# 03_UI_Outputs.net
KiCad netlist of a schematic drawn in Altium Designer
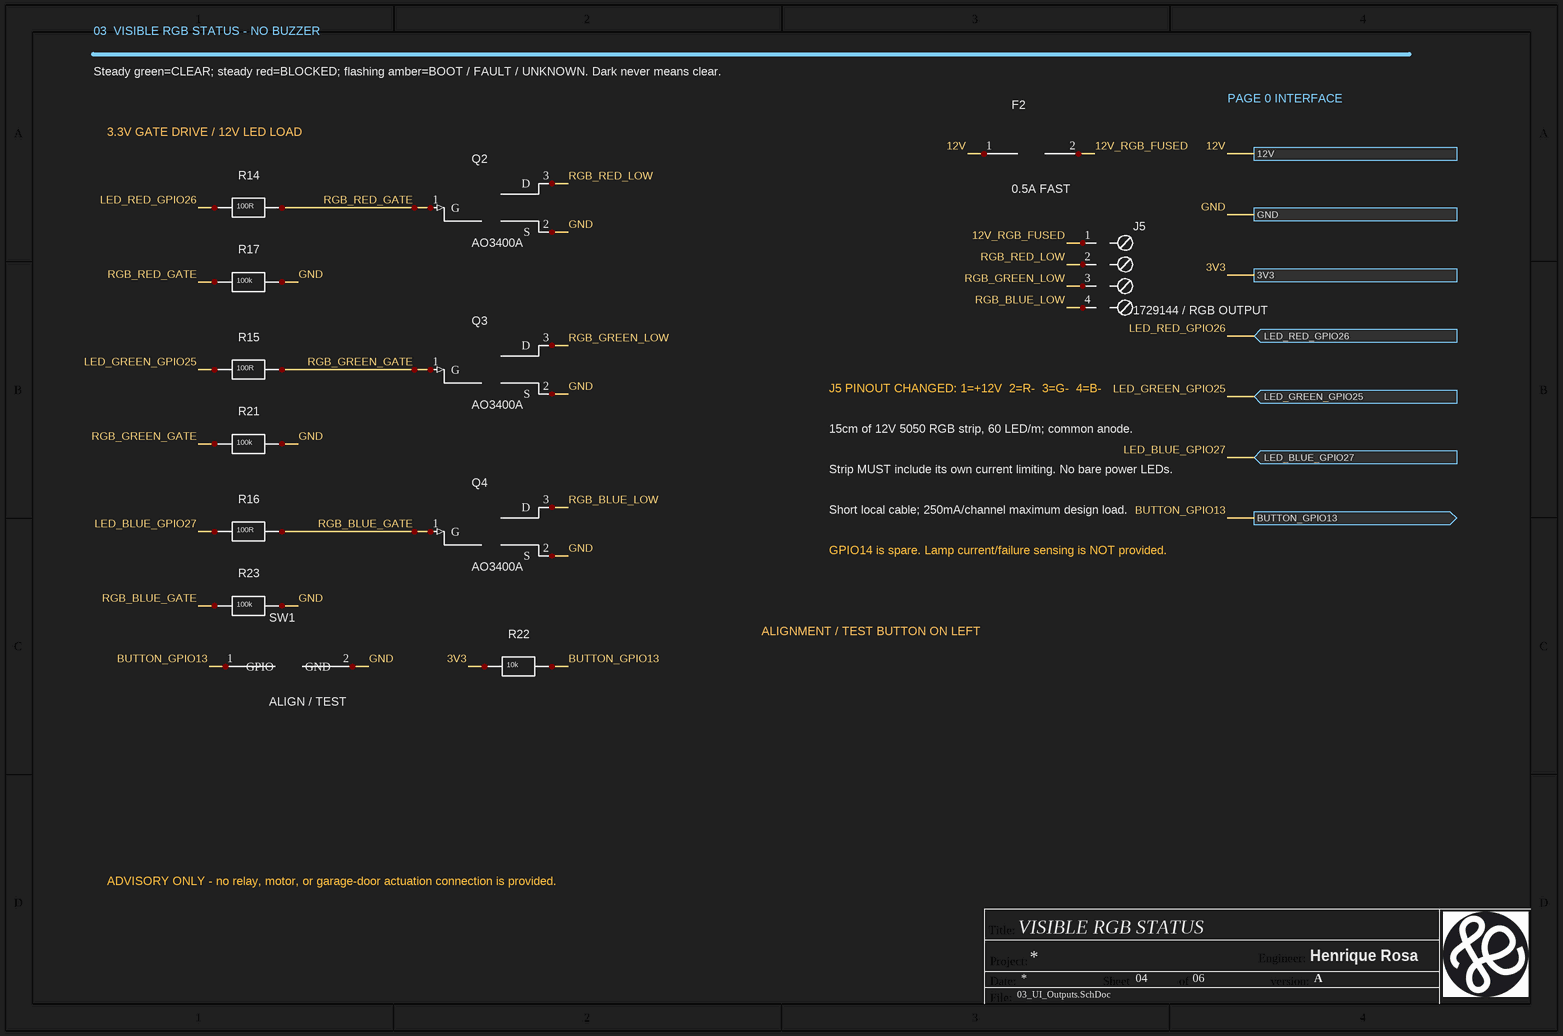
[diagram p0: 03_UI_Outputs.SchDoc]

(export (version "E")
  (design (tool "Eeschema 10.0.6"))
  (components
    (comp (ref "F2")
      (value "0.5A FAST")
      (footprint "PinRepairFootprints:LITTELFUSE_0451_2410")
      (description "RGB cable branch fuse; verify fault clearing with selected supply")
      (fields
        (field (name "MANUFACTURER") "Littelfuse")
        (field (name "MANUFACTURER PART NUMBER") "0451.500MRL")
      )
      (libsource (lib "ReviewedComponents_20260912-233454") (part "0451_500MRL__F2_view"))
    )
    (comp (ref "J5")
      (value "1729144 / RGB OUTPUT")
      (footprint "PartSpecificFootprints:PHOENIX_1729144_MKDSN_4_508")
      (description "Common-anode analogue RGB strip; NOT addressable")
      (fields
        (field (name "MANUFACTURER") "Phoenix Contact")
        (field (name "MANUFACTURER PART NUMBER") "1729144")
      )
      (libsource (lib "ReviewedComponents_20260912-233454") (part "1729144__J5_view"))
    )
    (comp (ref "Q2")
      (value "AO3400A")
      (footprint "PinRepairFootprints:AO3400A_G1_S2_D3")
      (description "30V NMOS; Rds(on) specified at Vgs=2.5V; limit load to 250mA/channel")
      (fields (field (name "MANUFACTURER") "Alpha and Omega Semiconductor"))
      (libsource (lib "ReviewedComponents_20260912-233454") (part "AO3400A__Q2_view"))
    )
    (comp (ref "Q3")
      (value "AO3400A")
      (footprint "PinRepairFootprints:AO3400A_G1_S2_D3")
      (description "30V NMOS; Rds(on) specified at Vgs=2.5V; limit load to 250mA/channel")
      (fields (field (name "MANUFACTURER") "Alpha and Omega Semiconductor"))
      (libsource (lib "ReviewedComponents_20260912-233454") (part "AO3400A__Q3_view"))
    )
    (comp (ref "Q4")
      (value "AO3400A")
      (footprint "PinRepairFootprints:AO3400A_G1_S2_D3")
      (description "30V NMOS; Rds(on) specified at Vgs=2.5V; limit load to 250mA/channel")
      (fields (field (name "MANUFACTURER") "Alpha and Omega Semiconductor"))
      (libsource (lib "ReviewedComponents_20260912-233454") (part "AO3400A__Q4_view"))
    )
    (comp (ref "R14")
      (value "100R")
      (footprint "PCB - RESISTOR - CHIP - YAGEO RES 0805_2012:YAGEO RES 0805_2012")
      (description "MOSFET gate series resistor")
      (fields (field (name "PART NUMBER") "RC0805FR-07100RL") (field (name "MANUFACTURER") "Yageo"))
      (libsource (lib "ReviewedComponents_20260912-233454") (part "RC0805FR-07100RL__R14_view"))
    )
    (comp (ref "R15")
      (value "100R")
      (footprint "PCB - RESISTOR - CHIP - YAGEO RES 0805_2012:YAGEO RES 0805_2012")
      (description "MOSFET gate series resistor")
      (fields (field (name "PART NUMBER") "RC0805FR-07100RL") (field (name "MANUFACTURER") "Yageo"))
      (libsource (lib "ReviewedComponents_20260912-233454") (part "RC0805FR-07100RL__R15_view"))
    )
    (comp (ref "R16")
      (value "100R")
      (footprint "PCB - RESISTOR - CHIP - YAGEO RES 0805_2012:YAGEO RES 0805_2012")
      (description "MOSFET gate series resistor")
      (fields (field (name "PART NUMBER") "RC0805FR-07100RL") (field (name "MANUFACTURER") "Yageo"))
      (libsource (lib "ReviewedComponents_20260912-233454") (part "RC0805FR-07100RL__R16_view"))
    )
    (comp (ref "R17")
      (value "100k")
      (footprint "PCB - RESISTOR - CHIP - YAGEO RES 0805_2012:YAGEO RES 0805_2012")
      (description "Gate-source pull-down; off while ESP32 resets")
      (fields (field (name "PART NUMBER") "RC0805FR-07100KL") (field (name "MANUFACTURER") "Yageo"))
      (libsource (lib "ReviewedComponents_20260912-233454") (part "RC0805FR-07100KL__R17_view"))
    )
    (comp (ref "R21")
      (value "100k")
      (footprint "PCB - RESISTOR - CHIP - YAGEO RES 0805_2012:YAGEO RES 0805_2012")
      (description "Gate-source pull-down; off while ESP32 resets")
      (fields (field (name "PART NUMBER") "RC0805FR-07100KL") (field (name "MANUFACTURER") "Yageo"))
      (libsource (lib "ReviewedComponents_20260912-233454") (part "RC0805FR-07100KL__R21_view"))
    )
    (comp (ref "R22")
      (value "10k")
      (footprint "PCB - RESISTOR - CHIP - YAGEO RES 0805_2012:YAGEO RES 0805_2012")
      (description "Test button external pull-up")
      (fields (field (name "PART NUMBER") "RC0805FR-0710KL") (field (name "MANUFACTURER") "Yageo"))
      (libsource (lib "ReviewedComponents_20260912-233454") (part "RC0805FR-0710KL__R22_view"))
    )
    (comp (ref "R23")
      (value "100k")
      (footprint "PCB - RESISTOR - CHIP - YAGEO RES 0805_2012:YAGEO RES 0805_2012")
      (description "Gate-source pull-down; off while ESP32 resets")
      (fields (field (name "PART NUMBER") "RC0805FR-07100KL") (field (name "MANUFACTURER") "Yageo"))
      (libsource (lib "ReviewedComponents_20260912-233454") (part "RC0805FR-07100KL__R23_view"))
    )
    (comp (ref "SW1")
      (value "ALIGN / TEST")
      (footprint "PinRepairFootprints:OMRON_B3FS1000P_LOGICAL_1_2")
      (description "Momentary test switch")
      (fields (field (name "MANUFACTURER") "Omron") (field (name "MANUFACTURER PART NUMBER") "B3FS-1000P"))
      (libsource (lib "ReviewedComponents_20260912-233454") (part "B3FS-1000P__SW1_view"))
    )
  )
  (nets
    (net (code "1") (name "/3V3") (class "Default")
      (node (ref "R22") (pin "1") (pinfunction "1_1") (pintype "passive"))
    )
    (net (code "2") (name "/12V") (class "Default") (node (ref "F2") (pin "1") (pintype "passive")))
    (net (code "3") (name "/12V_RGB_FUSED") (class "Default")
      (node (ref "F2") (pin "2") (pintype "passive"))
      (node (ref "J5") (pin "1") (pinfunction "+12V_1") (pintype "power_in"))
    )
    (net (code "4") (name "/BUTTON_GPIO13") (class "Default")
      (node (ref "R22") (pin "2") (pinfunction "2_2") (pintype "passive"))
      (node (ref "SW1") (pin "1") (pinfunction "GPIO_1") (pintype "passive"))
    )
    (net (code "5") (name "/GND") (class "Default")
      (node (ref "Q2") (pin "2") (pinfunction "S_2") (pintype "passive"))
      (node (ref "Q3") (pin "2") (pinfunction "S_2") (pintype "passive"))
      (node (ref "Q4") (pin "2") (pinfunction "S_2") (pintype "passive"))
      (node (ref "R17") (pin "2") (pinfunction "2_2") (pintype "passive"))
      (node (ref "R21") (pin "2") (pinfunction "2_2") (pintype "passive"))
      (node (ref "R23") (pin "2") (pinfunction "2_2") (pintype "passive"))
      (node (ref "SW1") (pin "2") (pinfunction "GND_2") (pintype "passive"))
    )
    (net (code "6") (name "/LED_BLUE_GPIO27") (class "Default")
      (node (ref "R16") (pin "1") (pinfunction "1_1") (pintype "passive"))
    )
    (net (code "7") (name "/LED_GREEN_GPIO25") (class "Default")
      (node (ref "R15") (pin "1") (pinfunction "1_1") (pintype "passive"))
    )
    (net (code "8") (name "/LED_RED_GPIO26") (class "Default")
      (node (ref "R14") (pin "1") (pinfunction "1_1") (pintype "passive"))
    )
    (net (code "9") (name "/RGB_BLUE_GATE") (class "Default")
      (node (ref "Q4") (pin "1") (pinfunction "G_1") (pintype "input"))
      (node (ref "R16") (pin "2") (pinfunction "2_2") (pintype "passive"))
      (node (ref "R23") (pin "1") (pinfunction "1_1") (pintype "passive"))
    )
    (net (code "10") (name "/RGB_BLUE_LOW") (class "Default")
      (node (ref "J5") (pin "4") (pinfunction "B-_4") (pintype "passive"))
      (node (ref "Q4") (pin "3") (pinfunction "D_3") (pintype "passive"))
    )
    (net (code "11") (name "/RGB_GREEN_GATE") (class "Default")
      (node (ref "Q3") (pin "1") (pinfunction "G_1") (pintype "input"))
      (node (ref "R15") (pin "2") (pinfunction "2_2") (pintype "passive"))
      (node (ref "R21") (pin "1") (pinfunction "1_1") (pintype "passive"))
    )
    (net (code "12") (name "/RGB_GREEN_LOW") (class "Default")
      (node (ref "J5") (pin "3") (pinfunction "G-_3") (pintype "passive"))
      (node (ref "Q3") (pin "3") (pinfunction "D_3") (pintype "passive"))
    )
    (net (code "13") (name "/RGB_RED_GATE") (class "Default")
      (node (ref "Q2") (pin "1") (pinfunction "G_1") (pintype "input"))
      (node (ref "R14") (pin "2") (pinfunction "2_2") (pintype "passive"))
      (node (ref "R17") (pin "1") (pinfunction "1_1") (pintype "passive"))
    )
    (net (code "14") (name "/RGB_RED_LOW") (class "Default")
      (node (ref "J5") (pin "2") (pinfunction "R-_2") (pintype "passive"))
      (node (ref "Q2") (pin "3") (pinfunction "D_3") (pintype "passive"))
    )
  )
)
